# abqmmf2018.net
KiCad netlist of a schematic drawn in EAGLE
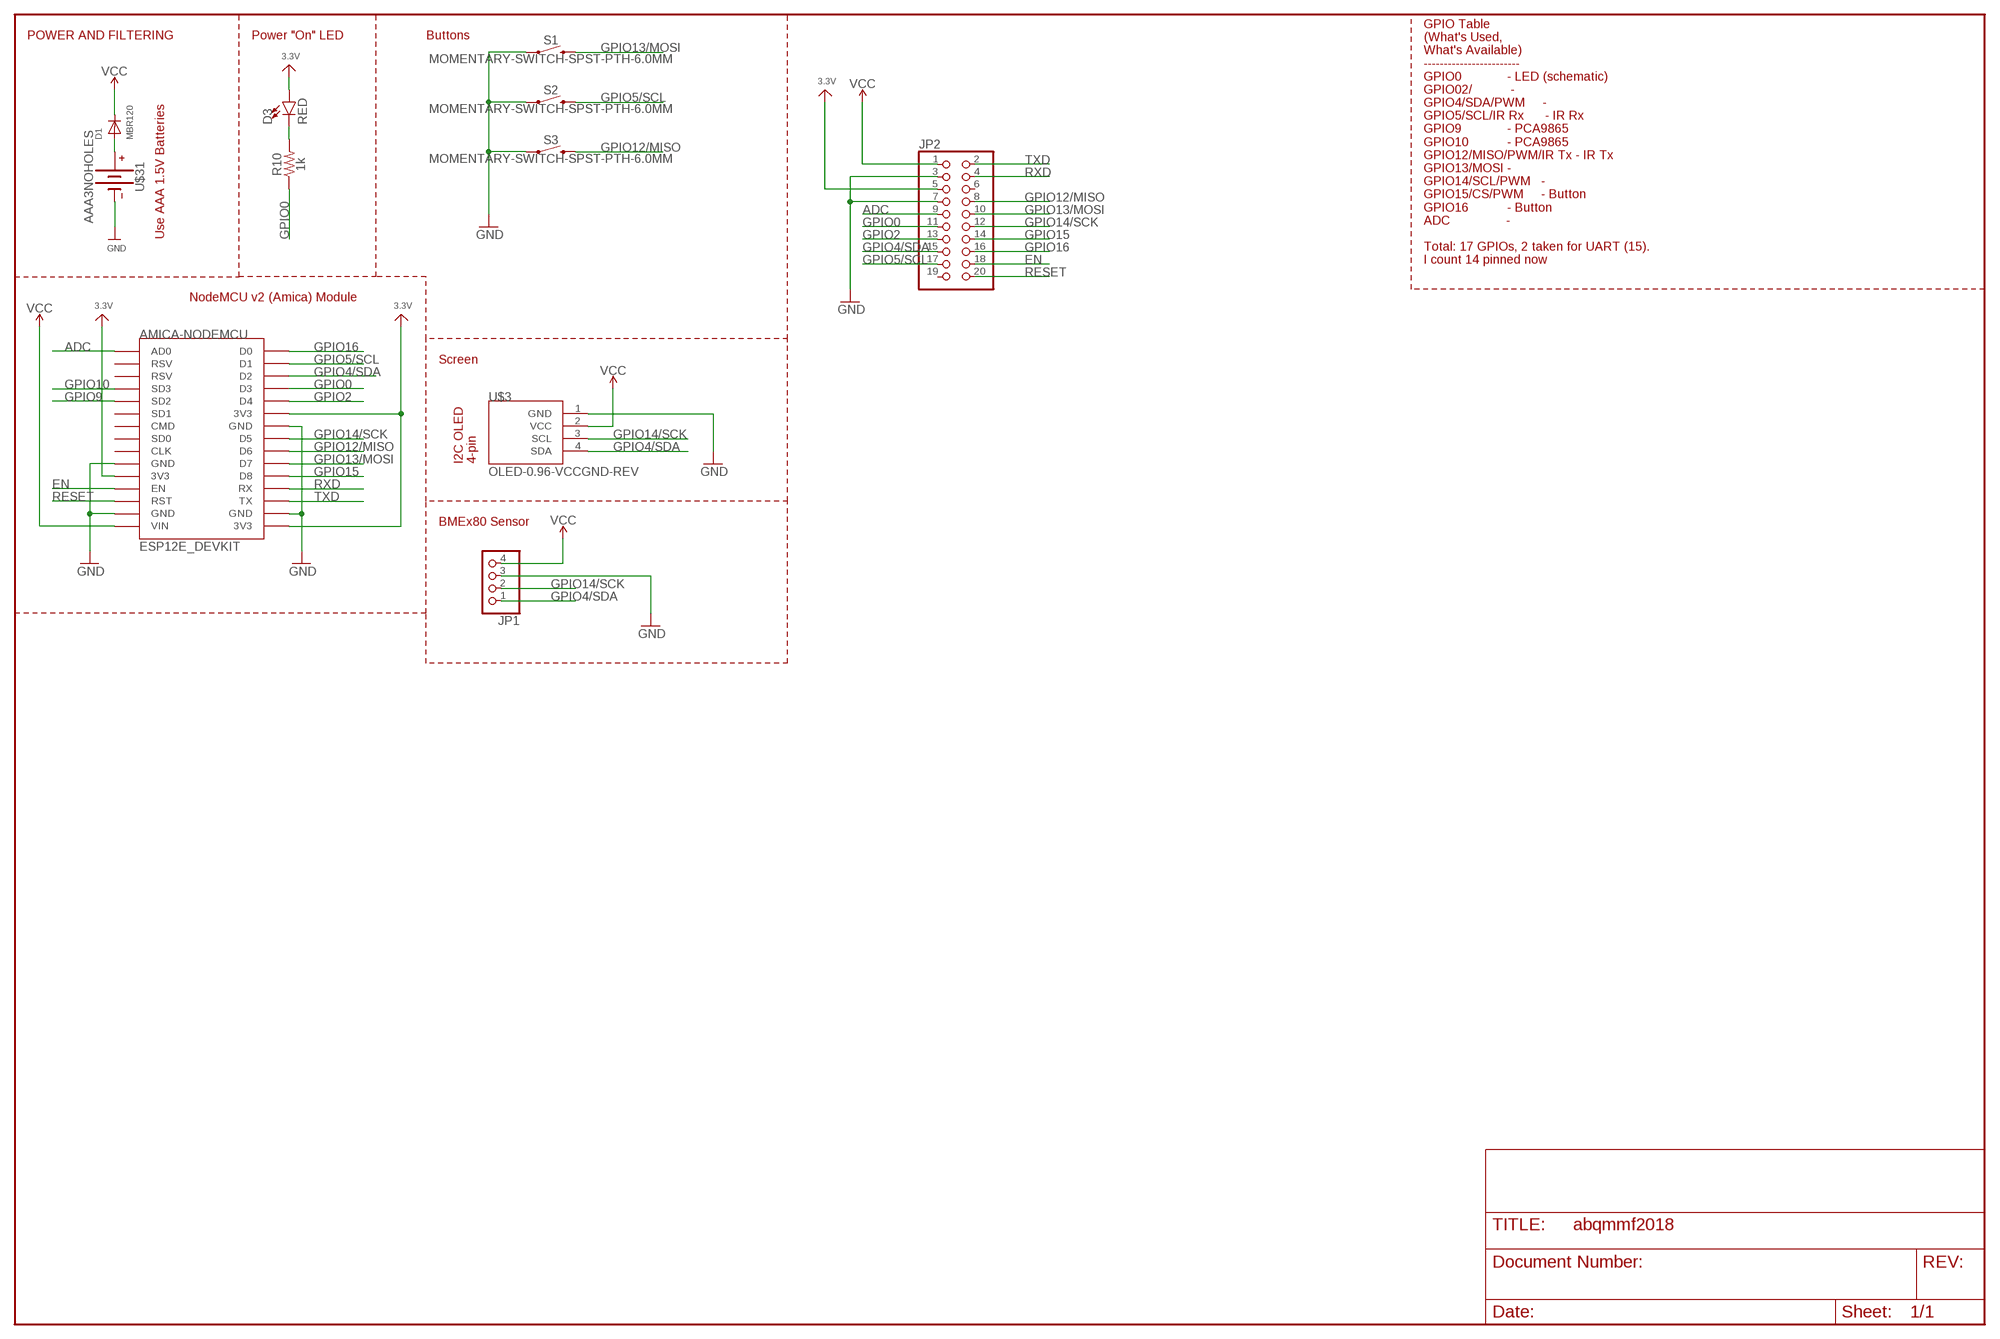
[diagram p0: schematic, sheet 1]

(export (version "E")
  (design (tool "Eeschema 10.0.6"))
  (components
    (comp (ref "AMICA-NODEMCU")
      (value "ESP12E_DEVKIT")
      (footprint "eagle-import:ESP12E_DEVKIT")
      (libsource (lib "eagle-import") (part "ESP12E_DEVKIT"))
    )
    (comp (ref "D1")
      (value "MBR120")
      (footprint "eagle-import:DO-1N4148")
      (libsource (lib "eagle-import") (part "DIODEDO-1N4148"))
    )
    (comp (ref "D3")
      (value "RED")
      (footprint "eagle-import:LED_5MM")
      (libsource (lib "eagle-import") (part "LED5MM"))
    )
    (comp (ref "JP1")
      (value "PINHD-1X4")
      (footprint "eagle-import:1X04")
      (libsource (lib "eagle-import") (part "PINHD-1X4"))
    )
    (comp (ref "JP2")
      (value "PINHD-2X10")
      (footprint "eagle-import:2X10")
      (libsource (lib "eagle-import") (part "PINHD-2X10"))
    )
    (comp (ref "R10")
      (value "1k")
      (footprint "eagle-import:AXIAL-0.3")
      (libsource (lib "eagle-import") (part "1KOHM-HORIZ-1/4W-1%"))
    )
    (comp (ref "S1")
      (value "MOMENTARY-SWITCH-SPST-PTH-6.0MM")
      (footprint "eagle-import:TACTILE_SWITCH_PTH_6.0MM")
      (libsource (lib "eagle-import") (part "MOMENTARY-SWITCH-SPST-PTH-6.0MM"))
    )
    (comp (ref "S2")
      (value "MOMENTARY-SWITCH-SPST-PTH-6.0MM")
      (footprint "eagle-import:TACTILE_SWITCH_PTH_6.0MM")
      (libsource (lib "eagle-import") (part "MOMENTARY-SWITCH-SPST-PTH-6.0MM"))
    )
    (comp (ref "S3")
      (value "MOMENTARY-SWITCH-SPST-PTH-6.0MM")
      (footprint "eagle-import:TACTILE_SWITCH_PTH_6.0MM")
      (libsource (lib "eagle-import") (part "MOMENTARY-SWITCH-SPST-PTH-6.0MM"))
    )
    (comp (ref "U$3")
      (value "OLED-0.96-VCCGND-REV")
      (footprint "eagle-import:OLED-I2C-4PIN-VCCGND-REV")
      (libsource (lib "eagle-import") (part "OLED-0.96-VCCGND-REV"))
    )
    (comp (ref "U$31")
      (value "AAA3NOHOLES")
      (footprint "eagle-import:AAA3-NOHOLES")
      (libsource (lib "eagle-import") (part "AAA3NOHOLES"))
    )
  )
  (nets
    (net (code "1") (name "/ADC") (class "Default")
      (node (ref "AMICA-NODEMCU") (pin "AD0") (pinfunction "AD0_AD0") (pintype "bidirectional"))
      (node (ref "JP2") (pin "9") (pinfunction "9_9") (pintype "passive"))
    )
    (net (code "2") (name "/EN") (class "Default")
      (node (ref "AMICA-NODEMCU") (pin "EN") (pinfunction "EN_EN") (pintype "bidirectional"))
      (node (ref "JP2") (pin "18") (pinfunction "18_18") (pintype "passive"))
    )
    (net (code "3") (name "/GPIO0") (class "Default")
      (node (ref "AMICA-NODEMCU") (pin "D3") (pinfunction "D3_D3") (pintype "bidirectional"))
      (node (ref "JP2") (pin "11") (pinfunction "11_11") (pintype "passive"))
      (node (ref "R10") (pin "P$1") (pinfunction "1_P$1") (pintype "passive"))
    )
    (net (code "4") (name "/GPIO2") (class "Default")
      (node (ref "AMICA-NODEMCU") (pin "D4") (pinfunction "D4_D4") (pintype "bidirectional"))
      (node (ref "JP2") (pin "13") (pinfunction "13_13") (pintype "passive"))
    )
    (net (code "5") (name "/GPIO4{slash}SDA") (class "Default")
      (node (ref "AMICA-NODEMCU") (pin "D2") (pinfunction "D2_D2") (pintype "bidirectional"))
      (node (ref "JP1") (pin "1") (pinfunction "1_1") (pintype "passive"))
      (node (ref "JP2") (pin "15") (pinfunction "15_15") (pintype "passive"))
      (node (ref "U$3") (pin "4") (pinfunction "SDA_4") (pintype "bidirectional"))
    )
    (net (code "6") (name "/GPIO5{slash}SCL") (class "Default")
      (node (ref "AMICA-NODEMCU") (pin "D1") (pinfunction "D1_D1") (pintype "bidirectional"))
      (node (ref "JP2") (pin "17") (pinfunction "17_17") (pintype "passive"))
      (node (ref "S2") (pin "3") (pinfunction "2_3") (pintype "passive"))
    )
    (net (code "7") (name "/GPIO9") (class "Default")
      (node (ref "AMICA-NODEMCU") (pin "SD2") (pinfunction "SD2_SD2") (pintype "bidirectional"))
    )
    (net (code "8") (name "/GPIO10") (class "Default")
      (node (ref "AMICA-NODEMCU") (pin "SD3") (pinfunction "SD3_SD3") (pintype "bidirectional"))
    )
    (net (code "9") (name "/GPIO12{slash}MISO") (class "Default")
      (node (ref "AMICA-NODEMCU") (pin "D6") (pinfunction "D6_D6") (pintype "bidirectional"))
      (node (ref "JP2") (pin "8") (pinfunction "8_8") (pintype "passive"))
      (node (ref "S3") (pin "3") (pinfunction "2_3") (pintype "passive"))
    )
    (net (code "10") (name "/GPIO13{slash}MOSI") (class "Default")
      (node (ref "AMICA-NODEMCU") (pin "D7") (pinfunction "D7_D7") (pintype "bidirectional"))
      (node (ref "JP2") (pin "10") (pinfunction "10_10") (pintype "passive"))
      (node (ref "S1") (pin "3") (pinfunction "2_3") (pintype "passive"))
    )
    (net (code "11") (name "/GPIO14{slash}SCK") (class "Default")
      (node (ref "AMICA-NODEMCU") (pin "D5") (pinfunction "D5_D5") (pintype "bidirectional"))
      (node (ref "JP1") (pin "2") (pinfunction "2_2") (pintype "passive"))
      (node (ref "JP2") (pin "12") (pinfunction "12_12") (pintype "passive"))
      (node (ref "U$3") (pin "3") (pinfunction "SCL_3") (pintype "bidirectional"))
    )
    (net (code "12") (name "/GPIO15") (class "Default")
      (node (ref "AMICA-NODEMCU") (pin "D8") (pinfunction "D8_D8") (pintype "bidirectional"))
      (node (ref "JP2") (pin "14") (pinfunction "14_14") (pintype "passive"))
    )
    (net (code "13") (name "/GPIO16") (class "Default")
      (node (ref "AMICA-NODEMCU") (pin "D0") (pinfunction "D0_D0") (pintype "bidirectional"))
      (node (ref "JP2") (pin "16") (pinfunction "16_16") (pintype "passive"))
    )
    (net (code "14") (name "/RESET") (class "Default")
      (node (ref "AMICA-NODEMCU") (pin "RST") (pinfunction "RST_RST") (pintype "bidirectional"))
      (node (ref "JP2") (pin "20") (pinfunction "20_20") (pintype "passive"))
    )
    (net (code "15") (name "/RXD") (class "Default")
      (node (ref "AMICA-NODEMCU") (pin "RX") (pinfunction "RX_RX") (pintype "bidirectional"))
      (node (ref "JP2") (pin "4") (pinfunction "4_4") (pintype "passive"))
    )
    (net (code "16") (name "/TXD") (class "Default")
      (node (ref "AMICA-NODEMCU") (pin "TX") (pinfunction "TX_TX") (pintype "bidirectional"))
      (node (ref "JP2") (pin "2") (pinfunction "2_2") (pintype "passive"))
    )
    (net (code "17") (name "3.3V") (class "Default")
      (node (ref "AMICA-NODEMCU") (pin "3V3@0") (pinfunction "3V3_3V3@0") (pintype "bidirectional"))
      (node (ref "AMICA-NODEMCU") (pin "3V3@1") (pinfunction "3V3_3V3@1") (pintype "bidirectional"))
      (node (ref "AMICA-NODEMCU") (pin "3V3@2") (pinfunction "3V3_3V3@2") (pintype "bidirectional"))
      (node (ref "D3") (pin "A") (pinfunction "A_A") (pintype "passive"))
      (node (ref "JP2") (pin "5") (pinfunction "5_5") (pintype "passive"))
    )
    (net (code "18") (name "GND") (class "Default")
      (node (ref "AMICA-NODEMCU") (pin "GND@0") (pinfunction "GND_GND@0") (pintype "bidirectional"))
      (node (ref "AMICA-NODEMCU") (pin "GND@1") (pinfunction "GND_GND@1") (pintype "bidirectional"))
      (node (ref "AMICA-NODEMCU") (pin "GND@2") (pinfunction "GND_GND@2") (pintype "bidirectional"))
      (node (ref "AMICA-NODEMCU") (pin "GND@3") (pinfunction "GND_GND@3") (pintype "bidirectional"))
      (node (ref "JP1") (pin "3") (pinfunction "3_3") (pintype "passive"))
      (node (ref "JP2") (pin "3") (pinfunction "3_3") (pintype "passive"))
      (node (ref "JP2") (pin "7") (pinfunction "7_7") (pintype "passive"))
      (node (ref "S1") (pin "1") (pinfunction "1_1") (pintype "passive"))
      (node (ref "S2") (pin "1") (pinfunction "1_1") (pintype "passive"))
      (node (ref "S3") (pin "1") (pinfunction "1_1") (pintype "passive"))
      (node (ref "U$3") (pin "1") (pinfunction "GND_1") (pintype "bidirectional"))
      (node (ref "U$31") (pin "NEG") (pinfunction "-_NEG") (pintype "power_in"))
    )
    (net (code "19") (name "Net-(D3-C)") (class "Default")
      (node (ref "D3") (pin "K") (pinfunction "C_K") (pintype "passive"))
      (node (ref "R10") (pin "P$2") (pinfunction "2_P$2") (pintype "passive"))
    )
    (net (code "20") (name "Net-(U$31-+)") (class "Default")
      (node (ref "D1") (pin "A") (pinfunction "A_A") (pintype "passive"))
      (node (ref "U$31") (pin "POS") (pinfunction "+_POS") (pintype "power_in"))
    )
    (net (code "21") (name "VCC") (class "Default")
      (node (ref "AMICA-NODEMCU") (pin "VIN") (pinfunction "VIN_VIN") (pintype "bidirectional"))
      (node (ref "D1") (pin "C") (pinfunction "C_C") (pintype "passive"))
      (node (ref "JP1") (pin "4") (pinfunction "4_4") (pintype "passive"))
      (node (ref "JP2") (pin "1") (pinfunction "1_1") (pintype "passive"))
      (node (ref "U$3") (pin "2") (pinfunction "VCC_2") (pintype "bidirectional"))
    )
    (net (code "22") (name "unconnected-(AMICA-NODEMCU-PadCLK)") (class "Default")
      (node (ref "AMICA-NODEMCU") (pin "CLK") (pinfunction "CLK_CLK") (pintype "bidirectional"))
    )
    (net (code "23") (name "unconnected-(AMICA-NODEMCU-PadCMD)") (class "Default")
      (node (ref "AMICA-NODEMCU") (pin "CMD") (pinfunction "CMD_CMD") (pintype "bidirectional"))
    )
    (net (code "24") (name "unconnected-(AMICA-NODEMCU-PadSD0)") (class "Default")
      (node (ref "AMICA-NODEMCU") (pin "SD0") (pinfunction "SD0_SD0") (pintype "bidirectional"))
    )
    (net (code "25") (name "unconnected-(AMICA-NODEMCU-PadSD1)") (class "Default")
      (node (ref "AMICA-NODEMCU") (pin "SD1") (pinfunction "SD1_SD1") (pintype "bidirectional"))
    )
    (net (code "26") (name "unconnected-(AMICA-NODEMCU-RSV-PadRSV@0)") (class "Default")
      (node (ref "AMICA-NODEMCU") (pin "RSV@0") (pinfunction "RSV_RSV@0") (pintype "bidirectional"))
    )
    (net (code "27") (name "unconnected-(AMICA-NODEMCU-RSV-PadRSV@1)") (class "Default")
      (node (ref "AMICA-NODEMCU") (pin "RSV@1") (pinfunction "RSV_RSV@1") (pintype "bidirectional"))
    )
    (net (code "28") (name "unconnected-(JP2-Pad6)") (class "Default")
      (node (ref "JP2") (pin "6") (pinfunction "6_6") (pintype "passive"))
    )
    (net (code "29") (name "unconnected-(JP2-Pad19)") (class "Default")
      (node (ref "JP2") (pin "19") (pinfunction "19_19") (pintype "passive"))
    )
  )
)
